# SmartCar_Arduino_V3.net
KiCad netlist of a schematic drawn in EAGLE
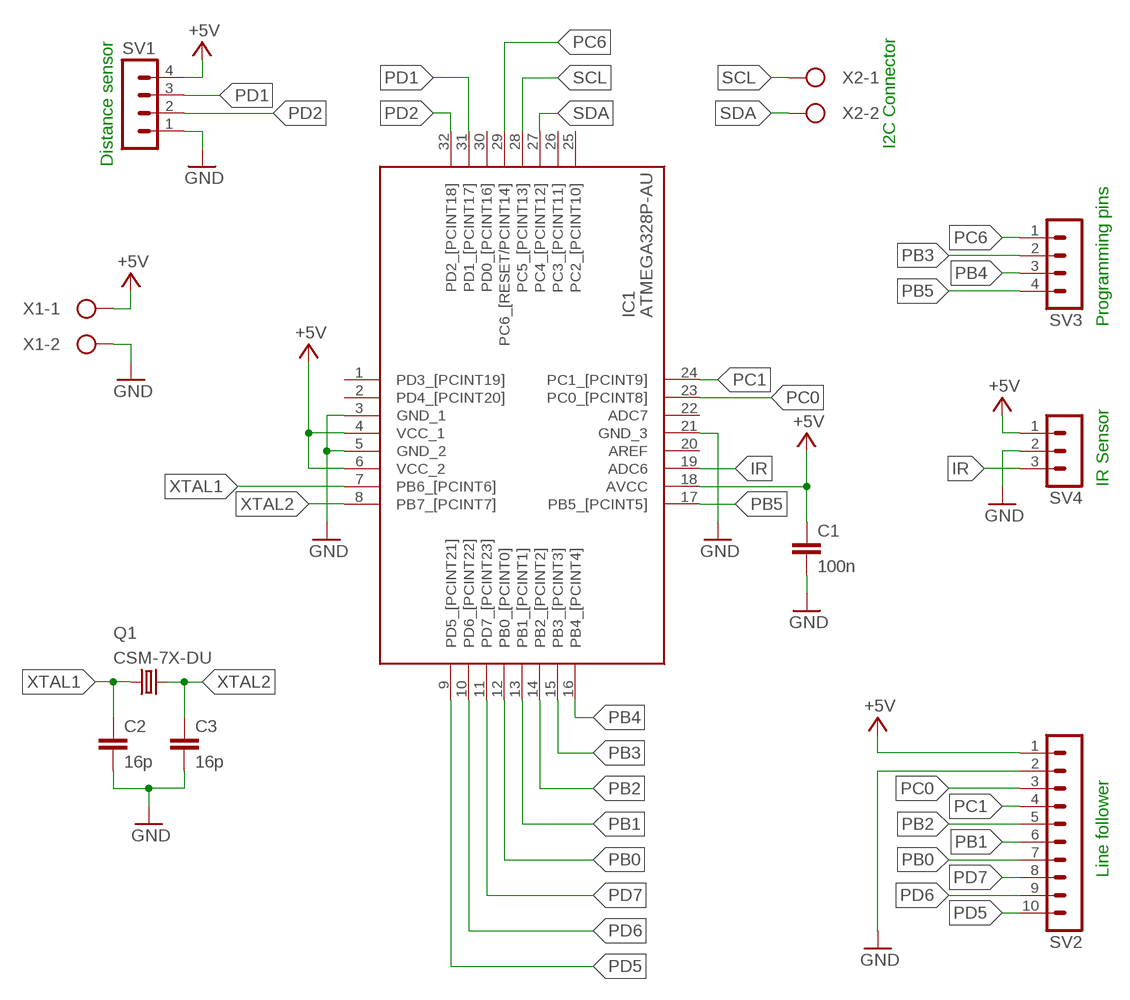
[diagram p0: schematic, sheet 1]

(export (version "E")
  (design (tool "Eeschema 10.0.6"))
  (components
    (comp (ref "C1")
      (value "100n")
      (footprint "eagle-import:C0805")
      (libsource (lib "eagle-import") (part "C-EUC0805"))
    )
    (comp (ref "C2")
      (value "16p")
      (footprint "eagle-import:C0805")
      (libsource (lib "eagle-import") (part "C-EUC0805"))
    )
    (comp (ref "C3")
      (value "16p")
      (footprint "eagle-import:C0805")
      (libsource (lib "eagle-import") (part "C-EUC0805"))
    )
    (comp (ref "IC1")
      (value "ATMEGA328P-AU")
      (footprint "eagle-import:QFP80P900X900X120-32N")
      (fields (field (name "MOUSER_PART_NUMBER") "556-ATMEGA328P-AU"))
      (libsource (lib "eagle-import") (part "ATMEGA328P-AU"))
    )
    (comp (ref "Q1")
      (value "CSM-7X-DU")
      (footprint "eagle-import:CSM-7X-DU")
      (libsource (lib "eagle-import") (part "CSM-7X-DU"))
    )
    (comp (ref "SV1")
      (value "MA04-1")
      (footprint "eagle-import:MA04-1")
      (libsource (lib "eagle-import") (part "MA04-1"))
    )
    (comp (ref "SV2")
      (value "MA10-1")
      (footprint "eagle-import:MA10-1")
      (libsource (lib "eagle-import") (part "MA10-1"))
    )
    (comp (ref "SV3")
      (value "MA04-1")
      (footprint "eagle-import:MA04-1")
      (libsource (lib "eagle-import") (part "MA04-1"))
    )
    (comp (ref "SV4")
      (value "MA03-1")
      (footprint "eagle-import:MA03-1")
      (libsource (lib "eagle-import") (part "MA03-1"))
    )
    (comp (ref "X1")
      (value "W237-102")
      (footprint "eagle-import:W237-102")
      (fields (field (name "MPN") "237-102"))
      (libsource (lib "eagle-import") (part "W237-102"))
    )
    (comp (ref "X2")
      (value "W237-102")
      (footprint "eagle-import:W237-102")
      (fields (field (name "MPN") "237-102"))
      (libsource (lib "eagle-import") (part "W237-102"))
    )
  )
  (nets
    (net (code "1") (name "+5V") (class "Default")
      (node (ref "C1") (pin "1") (pinfunction "1_1") (pintype "passive"))
      (node (ref "IC1") (pin "18") (pinfunction "AVCC_18") (pintype "power_in"))
      (node (ref "IC1") (pin "4") (pinfunction "VCC_1_4") (pintype "power_in"))
      (node (ref "IC1") (pin "6") (pinfunction "VCC_2_6") (pintype "power_in"))
      (node (ref "SV1") (pin "4") (pinfunction "4_4") (pintype "passive"))
      (node (ref "SV2") (pin "1") (pinfunction "1_1") (pintype "passive"))
      (node (ref "SV4") (pin "1") (pinfunction "1_1") (pintype "passive"))
      (node (ref "X1") (pin "1") (pinfunction "KL_1") (pintype "passive"))
    )
    (net (code "2") (name "GND") (class "Default")
      (node (ref "C1") (pin "2") (pinfunction "2_2") (pintype "passive"))
      (node (ref "C2") (pin "2") (pinfunction "2_2") (pintype "passive"))
      (node (ref "C3") (pin "2") (pinfunction "2_2") (pintype "passive"))
      (node (ref "IC1") (pin "21") (pinfunction "GND_3_21") (pintype "power_in"))
      (node (ref "IC1") (pin "3") (pinfunction "GND_1_3") (pintype "power_in"))
      (node (ref "IC1") (pin "5") (pinfunction "GND_2_5") (pintype "power_in"))
      (node (ref "SV1") (pin "1") (pinfunction "1_1") (pintype "passive"))
      (node (ref "SV2") (pin "2") (pinfunction "2_2") (pintype "passive"))
      (node (ref "SV4") (pin "2") (pinfunction "2_2") (pintype "passive"))
      (node (ref "X1") (pin "2") (pinfunction "KL_2") (pintype "passive"))
    )
    (net (code "3") (name "IR") (class "Default")
      (node (ref "IC1") (pin "19") (pinfunction "ADC6_19") (pintype "bidirectional"))
      (node (ref "SV4") (pin "3") (pinfunction "3_3") (pintype "passive"))
    )
    (net (code "4") (name "PB0") (class "Default")
      (node (ref "IC1") (pin "12") (pinfunction "PB0_[PCINT0]_12") (pintype "bidirectional"))
      (node (ref "SV2") (pin "7") (pinfunction "7_7") (pintype "passive"))
    )
    (net (code "5") (name "PB1") (class "Default")
      (node (ref "IC1") (pin "13") (pinfunction "PB1_[PCINT1]_13") (pintype "bidirectional"))
      (node (ref "SV2") (pin "6") (pinfunction "6_6") (pintype "passive"))
    )
    (net (code "6") (name "PB2") (class "Default")
      (node (ref "IC1") (pin "14") (pinfunction "PB2_[PCINT2]_14") (pintype "bidirectional"))
      (node (ref "SV2") (pin "5") (pinfunction "5_5") (pintype "passive"))
    )
    (net (code "7") (name "PB3") (class "Default")
      (node (ref "IC1") (pin "15") (pinfunction "PB3_[PCINT3]_15") (pintype "bidirectional"))
      (node (ref "SV3") (pin "2") (pinfunction "2_2") (pintype "passive"))
    )
    (net (code "8") (name "PB4") (class "Default")
      (node (ref "IC1") (pin "16") (pinfunction "PB4_[PCINT4]_16") (pintype "bidirectional"))
      (node (ref "SV3") (pin "3") (pinfunction "3_3") (pintype "passive"))
    )
    (net (code "9") (name "PB5") (class "Default")
      (node (ref "IC1") (pin "17") (pinfunction "PB5_[PCINT5]_17") (pintype "bidirectional"))
      (node (ref "SV3") (pin "4") (pinfunction "4_4") (pintype "passive"))
    )
    (net (code "10") (name "PC0") (class "Default")
      (node (ref "IC1") (pin "23") (pinfunction "PC0_[PCINT8]_23") (pintype "bidirectional"))
      (node (ref "SV2") (pin "3") (pinfunction "3_3") (pintype "passive"))
    )
    (net (code "11") (name "PC1") (class "Default")
      (node (ref "IC1") (pin "24") (pinfunction "PC1_[PCINT9]_24") (pintype "bidirectional"))
      (node (ref "SV2") (pin "4") (pinfunction "4_4") (pintype "passive"))
    )
    (net (code "12") (name "PC6") (class "Default")
      (node (ref "IC1") (pin "29") (pinfunction "PC6_[RESET/PCINT14]_29") (pintype "bidirectional"))
      (node (ref "SV3") (pin "1") (pinfunction "1_1") (pintype "passive"))
    )
    (net (code "13") (name "PD1") (class "Default")
      (node (ref "IC1") (pin "31") (pinfunction "PD1_[PCINT17]_31") (pintype "bidirectional"))
      (node (ref "SV1") (pin "3") (pinfunction "3_3") (pintype "passive"))
    )
    (net (code "14") (name "PD2") (class "Default")
      (node (ref "IC1") (pin "32") (pinfunction "PD2_[PCINT18]_32") (pintype "bidirectional"))
      (node (ref "SV1") (pin "2") (pinfunction "2_2") (pintype "passive"))
    )
    (net (code "15") (name "PD5") (class "Default")
      (node (ref "IC1") (pin "9") (pinfunction "PD5_[PCINT21]_9") (pintype "bidirectional"))
      (node (ref "SV2") (pin "10") (pinfunction "10_10") (pintype "passive"))
    )
    (net (code "16") (name "PD6") (class "Default")
      (node (ref "IC1") (pin "10") (pinfunction "PD6_[PCINT22]_10") (pintype "bidirectional"))
      (node (ref "SV2") (pin "9") (pinfunction "9_9") (pintype "passive"))
    )
    (net (code "17") (name "PD7") (class "Default")
      (node (ref "IC1") (pin "11") (pinfunction "PD7_[PCINT23]_11") (pintype "bidirectional"))
      (node (ref "SV2") (pin "8") (pinfunction "8_8") (pintype "passive"))
    )
    (net (code "18") (name "SCL") (class "Default")
      (node (ref "IC1") (pin "28") (pinfunction "PC5_[PCINT13]_28") (pintype "bidirectional"))
      (node (ref "X2") (pin "1") (pinfunction "KL_1") (pintype "passive"))
    )
    (net (code "19") (name "SDA") (class "Default")
      (node (ref "IC1") (pin "27") (pinfunction "PC4_[PCINT12]_27") (pintype "bidirectional"))
      (node (ref "X2") (pin "2") (pinfunction "KL_2") (pintype "passive"))
    )
    (net (code "20") (name "XTAL1") (class "Default")
      (node (ref "C2") (pin "1") (pinfunction "1_1") (pintype "passive"))
      (node (ref "IC1") (pin "7") (pinfunction "PB6_[PCINT6]_7") (pintype "bidirectional"))
      (node (ref "Q1") (pin "1") (pinfunction "1_1") (pintype "passive"))
    )
    (net (code "21") (name "XTAL2") (class "Default")
      (node (ref "C3") (pin "1") (pinfunction "1_1") (pintype "passive"))
      (node (ref "IC1") (pin "8") (pinfunction "PB7_[PCINT7]_8") (pintype "bidirectional"))
      (node (ref "Q1") (pin "2") (pinfunction "2_2") (pintype "passive"))
    )
    (net (code "22") (name "unconnected-(IC1-ADC7-Pad22)") (class "Default")
      (node (ref "IC1") (pin "22") (pinfunction "ADC7_22") (pintype "bidirectional"))
    )
    (net (code "23") (name "unconnected-(IC1-AREF-Pad20)") (class "Default")
      (node (ref "IC1") (pin "20") (pinfunction "AREF_20") (pintype "bidirectional"))
    )
    (net (code "24") (name "unconnected-(IC1-PC2_[PCINT10]-Pad25)") (class "Default")
      (node (ref "IC1") (pin "25") (pinfunction "PC2_[PCINT10]_25") (pintype "bidirectional"))
    )
    (net (code "25") (name "unconnected-(IC1-PC3_[PCINT11]-Pad26)") (class "Default")
      (node (ref "IC1") (pin "26") (pinfunction "PC3_[PCINT11]_26") (pintype "bidirectional"))
    )
    (net (code "26") (name "unconnected-(IC1-PD0_[PCINT16]-Pad30)") (class "Default")
      (node (ref "IC1") (pin "30") (pinfunction "PD0_[PCINT16]_30") (pintype "bidirectional"))
    )
    (net (code "27") (name "unconnected-(IC1-PD3_[PCINT19]-Pad1)") (class "Default")
      (node (ref "IC1") (pin "1") (pinfunction "PD3_[PCINT19]_1") (pintype "bidirectional"))
    )
    (net (code "28") (name "unconnected-(IC1-PD4_[PCINT20]-Pad2)") (class "Default")
      (node (ref "IC1") (pin "2") (pinfunction "PD4_[PCINT20]_2") (pintype "bidirectional"))
    )
  )
)
